# ROwen_thermocouple.net
KiCad netlist of a schematic drawn in EAGLE
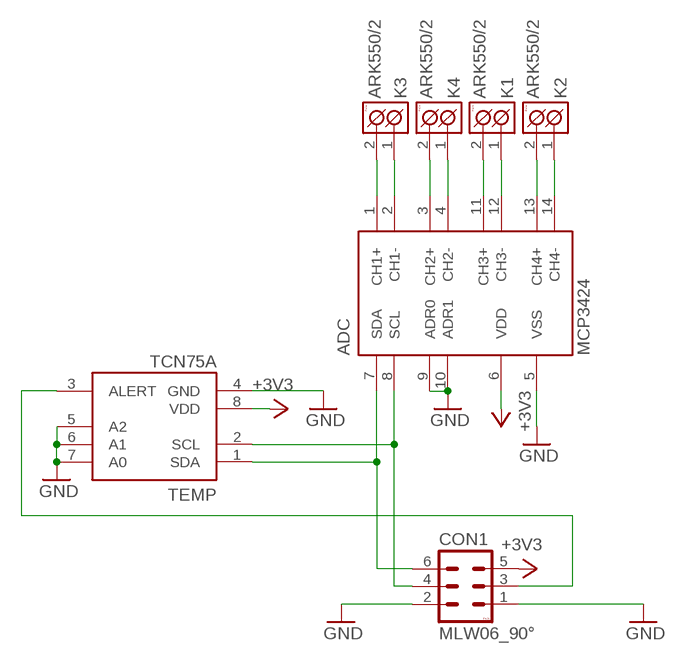
[diagram p0: schematic, sheet 1]

(export (version "E")
  (design (tool "Eeschema 10.0.6"))
  (components
    (comp (ref "ADC")
      (value "MCP3424")
      (footprint "eagle-import:TSSOP14")
      (libsource (lib "eagle-import") (part "MCP3424TSSOP14"))
    )
    (comp (ref "CON1")
      (value "MLW06_90°")
      (footprint "eagle-import:MLW06A")
      (libsource (lib "eagle-import") (part "MLW06_90°"))
    )
    (comp (ref "K1")
      (value "ARK550/2")
      (footprint "eagle-import:ARK550_2")
      (libsource (lib "eagle-import") (part "ARK550/2"))
    )
    (comp (ref "K2")
      (value "ARK550/2")
      (footprint "eagle-import:ARK550_2")
      (libsource (lib "eagle-import") (part "ARK550/2"))
    )
    (comp (ref "K3")
      (value "ARK550/2")
      (footprint "eagle-import:ARK550_2")
      (libsource (lib "eagle-import") (part "ARK550/2"))
    )
    (comp (ref "K4")
      (value "ARK550/2")
      (footprint "eagle-import:ARK550_2")
      (libsource (lib "eagle-import") (part "ARK550/2"))
    )
    (comp (ref "TEMP")
      (value "TCN75A")
      (footprint "eagle-import:SO8")
      (libsource (lib "eagle-import") (part "TCN75A"))
    )
  )
  (nets
    (net (code "1") (name "+3V3") (class "Default")
      (node (ref "ADC") (pin "6") (pinfunction "VDD_6") (pintype "power_in"))
      (node (ref "CON1") (pin "5") (pinfunction "5_5") (pintype "passive"))
      (node (ref "TEMP") (pin "8") (pinfunction "VDD_8") (pintype "power_in"))
    )
    (net (code "2") (name "GND") (class "Default")
      (node (ref "ADC") (pin "10") (pinfunction "ADR1_10") (pintype "bidirectional"))
      (node (ref "ADC") (pin "5") (pinfunction "VSS_5") (pintype "power_in"))
      (node (ref "ADC") (pin "9") (pinfunction "ADR0_9") (pintype "bidirectional"))
      (node (ref "CON1") (pin "1") (pinfunction "1_1") (pintype "passive"))
      (node (ref "CON1") (pin "2") (pinfunction "2_2") (pintype "passive"))
      (node (ref "TEMP") (pin "4") (pinfunction "GND_4") (pintype "power_in"))
      (node (ref "TEMP") (pin "5") (pinfunction "A2_5") (pintype "bidirectional"))
      (node (ref "TEMP") (pin "6") (pinfunction "A1_6") (pintype "bidirectional"))
      (node (ref "TEMP") (pin "7") (pinfunction "A0_7") (pintype "bidirectional"))
    )
    (net (code "3") (name "Net-(ADC-CH1+)") (class "Default")
      (node (ref "ADC") (pin "1") (pinfunction "CH1+_1") (pintype "bidirectional"))
      (node (ref "K3") (pin "2") (pinfunction "K2_2") (pintype "passive"))
    )
    (net (code "4") (name "Net-(ADC-CH1-)") (class "Default")
      (node (ref "ADC") (pin "2") (pinfunction "CH1-_2") (pintype "bidirectional"))
      (node (ref "K3") (pin "1") (pinfunction "K1_1") (pintype "passive"))
    )
    (net (code "5") (name "Net-(ADC-CH2+)") (class "Default")
      (node (ref "ADC") (pin "3") (pinfunction "CH2+_3") (pintype "bidirectional"))
      (node (ref "K4") (pin "2") (pinfunction "K2_2") (pintype "passive"))
    )
    (net (code "6") (name "Net-(ADC-CH2-)") (class "Default")
      (node (ref "ADC") (pin "4") (pinfunction "CH2-_4") (pintype "bidirectional"))
      (node (ref "K4") (pin "1") (pinfunction "K1_1") (pintype "passive"))
    )
    (net (code "7") (name "Net-(ADC-CH3+)") (class "Default")
      (node (ref "ADC") (pin "11") (pinfunction "CH3+_11") (pintype "bidirectional"))
      (node (ref "K1") (pin "2") (pinfunction "K2_2") (pintype "passive"))
    )
    (net (code "8") (name "Net-(ADC-CH3-)") (class "Default")
      (node (ref "ADC") (pin "12") (pinfunction "CH3-_12") (pintype "bidirectional"))
      (node (ref "K1") (pin "1") (pinfunction "K1_1") (pintype "passive"))
    )
    (net (code "9") (name "Net-(ADC-CH4+)") (class "Default")
      (node (ref "ADC") (pin "13") (pinfunction "CH4+_13") (pintype "bidirectional"))
      (node (ref "K2") (pin "2") (pinfunction "K2_2") (pintype "passive"))
    )
    (net (code "10") (name "Net-(ADC-CH4-)") (class "Default")
      (node (ref "ADC") (pin "14") (pinfunction "CH4-_14") (pintype "bidirectional"))
      (node (ref "K2") (pin "1") (pinfunction "K1_1") (pintype "passive"))
    )
    (net (code "11") (name "Net-(ADC-SCL)") (class "Default")
      (node (ref "ADC") (pin "8") (pinfunction "SCL_8") (pintype "bidirectional"))
      (node (ref "CON1") (pin "4") (pinfunction "4_4") (pintype "passive"))
      (node (ref "TEMP") (pin "2") (pinfunction "SCL_2") (pintype "bidirectional"))
    )
    (net (code "12") (name "Net-(ADC-SDA)") (class "Default")
      (node (ref "ADC") (pin "7") (pinfunction "SDA_7") (pintype "bidirectional"))
      (node (ref "CON1") (pin "6") (pinfunction "6_6") (pintype "passive"))
      (node (ref "TEMP") (pin "1") (pinfunction "SDA_1") (pintype "bidirectional"))
    )
    (net (code "13") (name "Net-(TEMP-ALERT)") (class "Default")
      (node (ref "CON1") (pin "3") (pinfunction "3_3") (pintype "passive"))
      (node (ref "TEMP") (pin "3") (pinfunction "ALERT_3") (pintype "bidirectional"))
    )
  )
)
